# Sallen.net
KiCad netlist of a schematic drawn in Altium Designer
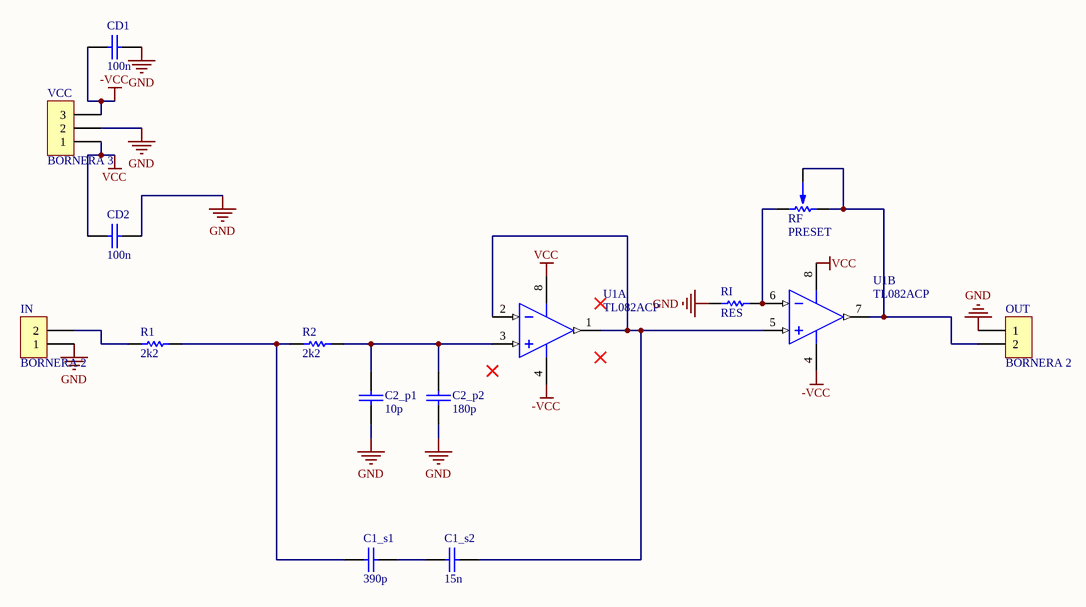
[diagram p0: Sallen.SchDoc]

(export (version "E")
  (design (tool "Eeschema 10.0.6"))
  (components
    (comp (ref "C1_s1") (value "390p") (footprint "0805") (libsource (lib "LIBEBAL") (part "CAP")))
    (comp (ref "C1_s2") (value "15n") (footprint "0805") (libsource (lib "LIBEBAL") (part "CAP")))
    (comp (ref "C2_p1") (value "10p") (footprint "0805") (libsource (lib "LIBEBAL") (part "CAP")))
    (comp (ref "C2_p2") (value "180p") (footprint "0805") (libsource (lib "LIBEBAL") (part "CAP")))
    (comp (ref "CD1") (value "100n") (footprint "0805") (libsource (lib "LIBEBAL") (part "CAP")))
    (comp (ref "CD2") (value "100n") (footprint "0805") (libsource (lib "LIBEBAL") (part "CAP")))
    (comp (ref "IN") (value "BORNERA 2") (footprint "BORNERA2") (libsource (lib "") (part "BORNERA 2_1")))
    (comp (ref "OUT")
      (value "BORNERA 2")
      (footprint "BORNERA2")
      (libsource (lib "LIB PIO IX") (part "BORNERA 2"))
    )
    (comp (ref "R1") (value "2k2") (footprint "0805") (libsource (lib "LIB PIO IX") (part "RES")))
    (comp (ref "R2") (value "2k2") (footprint "0805") (libsource (lib "LIB PIO IX") (part "RES")))
    (comp (ref "RF") (value "PRESET") (footprint "PRESET V") (libsource (lib "LIBEBAL") (part "PRESET")))
    (comp (ref "RI") (value "RES") (footprint "0805") (libsource (lib "LIB PIO IX") (part "RES")))
    (comp (ref "U1")
      (value "TL082ACP")
      (footprint "TI-P8")
      (description "JFET-Input Operational Amplifier, 7 to 36 V, 0 to 70 degC, 8-pin DIP (P8), Pb-Free (RoHS)")
      (fields (field (name "MANUFACTURER") "Texas Instruments"))
      (libsource (lib "TI Amplifiers and Linear Operational Amplifier General Purpose") (part "TL082ACP"))
    )
    (comp (ref "VCC")
      (value "BORNERA 3")
      (footprint "BORNERA3")
      (libsource (lib "LIB PIO IX") (part "BORNERA 3"))
    )
  )
  (nets
    (net (code "1") (name "-VCC") (class "Default")
      (node (ref "CD1") (pin "1") (pinfunction "1_1") (pintype "passive"))
      (node (ref "U1") (pin "4") (pinfunction "VCC-_4") (pintype "power_in"))
      (node (ref "VCC") (pin "3") (pinfunction "3_3") (pintype "passive"))
    )
    (net (code "2") (name "GND") (class "Default")
      (node (ref "C2_p1") (pin "2") (pinfunction "2_2") (pintype "passive"))
      (node (ref "C2_p2") (pin "2") (pinfunction "2_2") (pintype "passive"))
      (node (ref "CD1") (pin "2") (pinfunction "2_2") (pintype "passive"))
      (node (ref "CD2") (pin "2") (pinfunction "2_2") (pintype "passive"))
      (node (ref "IN") (pin "1") (pinfunction "1_1") (pintype "passive"))
      (node (ref "OUT") (pin "1") (pinfunction "1_1") (pintype "passive"))
      (node (ref "RI") (pin "1") (pinfunction "1_1") (pintype "passive"))
      (node (ref "VCC") (pin "2") (pinfunction "2_2") (pintype "passive"))
    )
    (net (code "3") (name "Net-(C1_s1-Pad1)") (class "Default")
      (node (ref "C1_s1") (pin "1") (pinfunction "1_1") (pintype "passive"))
      (node (ref "R1") (pin "1") (pinfunction "1_1") (pintype "passive"))
      (node (ref "R2") (pin "2") (pinfunction "2_2") (pintype "passive"))
    )
    (net (code "4") (name "Net-(C1_s1-Pad2)") (class "Default")
      (node (ref "C1_s1") (pin "2") (pinfunction "2_2") (pintype "passive"))
      (node (ref "C1_s2") (pin "1") (pinfunction "1_1") (pintype "passive"))
    )
    (net (code "5") (name "Net-(IN-Pad2)") (class "Default")
      (node (ref "IN") (pin "2") (pinfunction "2_2") (pintype "passive"))
      (node (ref "R1") (pin "2") (pinfunction "2_2") (pintype "passive"))
    )
    (net (code "6") (name "Net-(U1A-IN1+)") (class "Default")
      (node (ref "C2_p1") (pin "1") (pinfunction "1_1") (pintype "passive"))
      (node (ref "C2_p2") (pin "1") (pinfunction "1_1") (pintype "passive"))
      (node (ref "R2") (pin "1") (pinfunction "1_1") (pintype "passive"))
      (node (ref "U1") (pin "3") (pinfunction "IN1+_3") (pintype "input"))
    )
    (net (code "7") (name "Net-(U1A-IN1-)") (class "Default")
      (node (ref "C1_s2") (pin "2") (pinfunction "2_2") (pintype "passive"))
      (node (ref "U1") (pin "1") (pinfunction "OUT1_1") (pintype "output"))
      (node (ref "U1") (pin "2") (pinfunction "IN1-_2") (pintype "input"))
      (node (ref "U1") (pin "5") (pinfunction "IN2+_5") (pintype "input"))
    )
    (net (code "8") (name "Net-(U1B-IN2-)") (class "Default")
      (node (ref "RF") (pin "1") (pinfunction "1_1") (pintype "passive"))
      (node (ref "RI") (pin "2") (pinfunction "2_2") (pintype "passive"))
      (node (ref "U1") (pin "6") (pinfunction "IN2-_6") (pintype "input"))
    )
    (net (code "9") (name "Net-(U1B-OUT2)") (class "Default")
      (node (ref "OUT") (pin "2") (pinfunction "2_2") (pintype "passive"))
      (node (ref "RF") (pin "2") (pinfunction "2_2") (pintype "passive"))
      (node (ref "RF") (pin "3") (pinfunction "3_3") (pintype "passive"))
      (node (ref "U1") (pin "7") (pinfunction "OUT2_7") (pintype "output"))
    )
    (net (code "10") (name "VCC") (class "Default")
      (node (ref "CD2") (pin "1") (pinfunction "1_1") (pintype "passive"))
      (node (ref "U1") (pin "8") (pinfunction "VCC+_8") (pintype "power_in"))
      (node (ref "VCC") (pin "1") (pinfunction "1_1") (pintype "passive"))
    )
  )
)
